# breakout.net
KiCad netlist of a schematic drawn in EAGLE
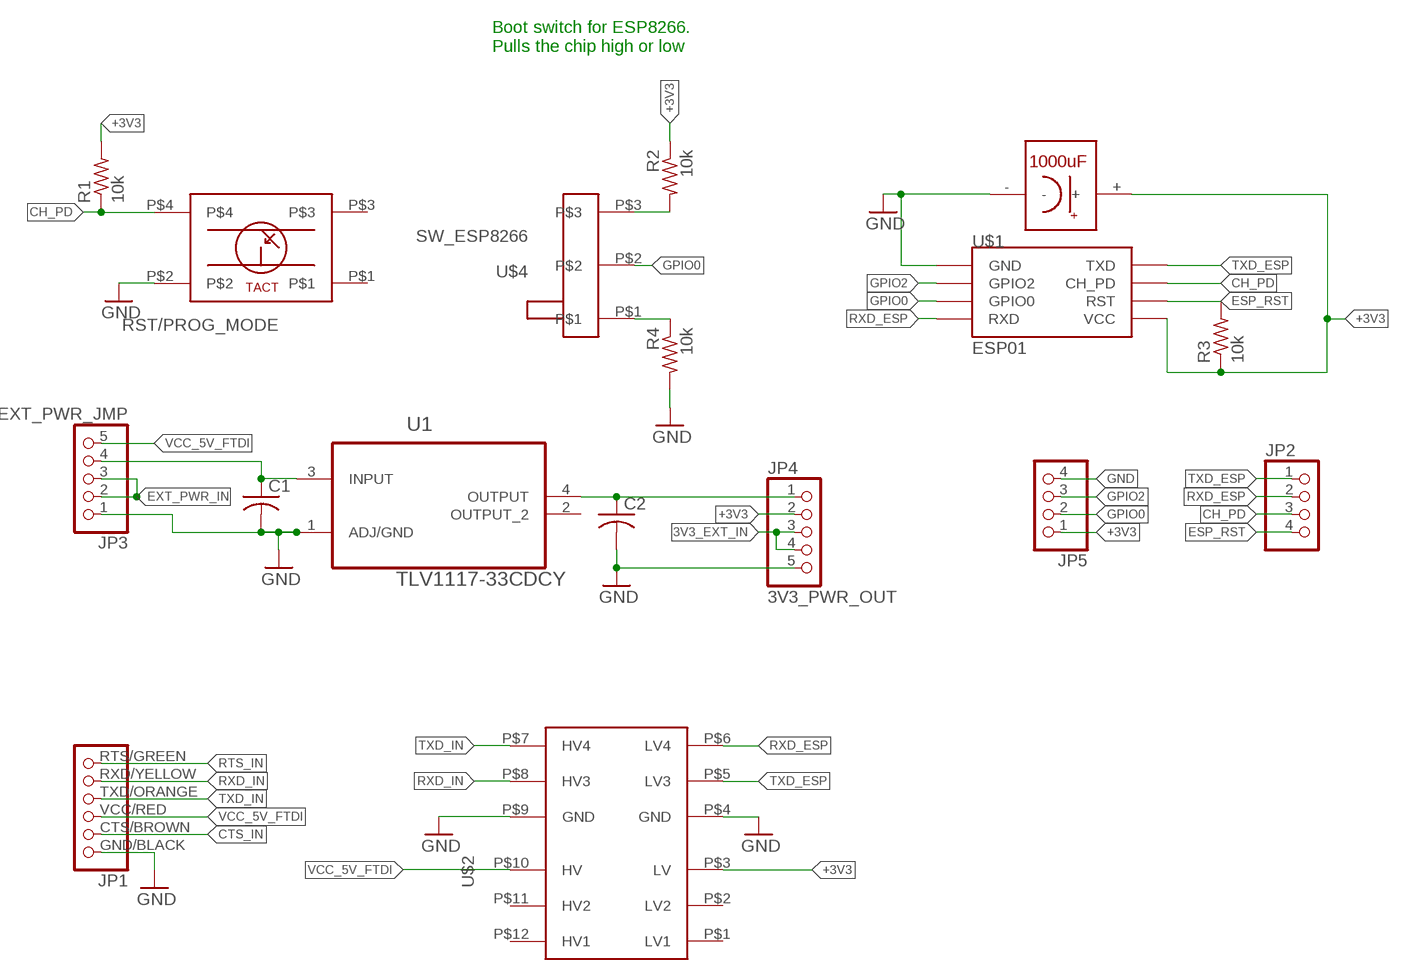
[diagram p0: schematic, sheet 1]

(export (version "E")
  (design (tool "Eeschema 10.0.6"))
  (components
    (comp (ref "C1")
      (value "C-USC0805K")
      (footprint "eagle-import:C0805K")
      (libsource (lib "eagle-import") (part "C-USC0805K"))
    )
    (comp (ref "C2")
      (value "C-USC0805K")
      (footprint "eagle-import:C0805K")
      (libsource (lib "eagle-import") (part "C-USC0805K"))
    )
    (comp (ref "JP1")
      (value "FTDI_CABLE")
      (footprint "eagle-import:FTDI_5V_SPARKFUN")
      (libsource (lib "eagle-import") (part "FTDI_CABLE"))
    )
    (comp (ref "JP2")
      (value "PINHD-1X4")
      (footprint "eagle-import:1X04")
      (libsource (lib "eagle-import") (part "PINHD-1X4"))
    )
    (comp (ref "JP3")
      (value "EXT_PWR_JMP")
      (footprint "eagle-import:1X05")
      (libsource (lib "eagle-import") (part "PINHD-1X5"))
    )
    (comp (ref "JP4")
      (value "3V3_PWR_OUT")
      (footprint "eagle-import:1X05")
      (libsource (lib "eagle-import") (part "PINHD-1X5"))
    )
    (comp (ref "JP5")
      (value "PINHD-1X4")
      (footprint "eagle-import:1X04")
      (libsource (lib "eagle-import") (part "PINHD-1X4"))
    )
    (comp (ref "R1")
      (value "10k")
      (footprint "eagle-import:R1206")
      (libsource (lib "eagle-import") (part "R-US_R1206"))
    )
    (comp (ref "R2")
      (value "10k")
      (footprint "eagle-import:R1206")
      (libsource (lib "eagle-import") (part "R-US_R1206"))
    )
    (comp (ref "R3")
      (value "10k")
      (footprint "eagle-import:R1206")
      (libsource (lib "eagle-import") (part "R-US_R1206"))
    )
    (comp (ref "R4")
      (value "10k")
      (footprint "eagle-import:R1206")
      (libsource (lib "eagle-import") (part "R-US_R1206"))
    )
    (comp (ref "RST/PROG_MODE")
      (value "TACT_SWITCH")
      (footprint "eagle-import:TACT")
      (libsource (lib "eagle-import") (part "TACT_SWITCH"))
    )
    (comp (ref "U$1")
      (value "ESP01")
      (footprint "eagle-import:ESP01")
      (libsource (lib "eagle-import") (part "ESP01"))
    )
    (comp (ref "U$2")
      (value "LVLSHIFTER")
      (footprint "eagle-import:LVLSFT_PAC")
      (libsource (lib "eagle-import") (part "LVLSHIFTER"))
    )
    (comp (ref "U$3")
      (value "TZVCAP")
      (footprint "eagle-import:TZV1000M")
      (libsource (lib "eagle-import") (part "TZVCAP"))
    )
    (comp (ref "U$4")
      (value "SW_ESP8266")
      (footprint "eagle-import:SW_PCB_ESP")
      (libsource (lib "eagle-import") (part "SW_ESP8266"))
    )
    (comp (ref "U1")
      (value "TLV1117-33CDCY")
      (footprint "eagle-import:SOT230P700X180-4N")
      (libsource (lib "eagle-import") (part "TLV1117-33CDCY"))
    )
  )
  (nets
    (net (code "1") (name "+3V3") (class "Default")
      (node (ref "JP4") (pin "2") (pinfunction "2_2") (pintype "passive"))
      (node (ref "JP5") (pin "1") (pinfunction "1_1") (pintype "passive"))
      (node (ref "R1") (pin "2") (pinfunction "2_2") (pintype "passive"))
      (node (ref "R2") (pin "1") (pinfunction "1_1") (pintype "passive"))
      (node (ref "R3") (pin "1") (pinfunction "1_1") (pintype "passive"))
      (node (ref "U$1") (pin "VCC") (pinfunction "VCC_VCC") (pintype "bidirectional"))
      (node (ref "U$2") (pin "P$3") (pinfunction "LV_P$3") (pintype "bidirectional"))
      (node (ref "U$3") (pin "+") (pinfunction "+_+") (pintype "bidirectional"))
    )
    (net (code "2") (name "3V3_EXT_IN") (class "Default")
      (node (ref "JP4") (pin "3") (pinfunction "3_3") (pintype "passive"))
      (node (ref "JP4") (pin "4") (pinfunction "4_4") (pintype "passive"))
    )
    (net (code "3") (name "CH_PD") (class "Default")
      (node (ref "JP2") (pin "3") (pinfunction "3_3") (pintype "passive"))
      (node (ref "R1") (pin "1") (pinfunction "1_1") (pintype "passive"))
      (node (ref "RST/PROG_MODE") (pin "P$4") (pinfunction "P$4_P$4") (pintype "bidirectional"))
      (node (ref "U$1") (pin "CH_PD") (pinfunction "CH_PD_CH_PD") (pintype "bidirectional"))
    )
    (net (code "4") (name "CTS_IN") (class "Default")
      (node (ref "JP1") (pin "CTS/BROWN") (pinfunction "2_CTS/BROWN") (pintype "passive"))
    )
    (net (code "5") (name "ESP_RST") (class "Default")
      (node (ref "JP2") (pin "4") (pinfunction "4_4") (pintype "passive"))
      (node (ref "R3") (pin "2") (pinfunction "2_2") (pintype "passive"))
      (node (ref "U$1") (pin "RST") (pinfunction "RST_RST") (pintype "bidirectional"))
    )
    (net (code "6") (name "EXT_PWR_IN") (class "Default")
      (node (ref "JP3") (pin "2") (pinfunction "2_2") (pintype "passive"))
      (node (ref "JP3") (pin "3") (pinfunction "3_3") (pintype "passive"))
    )
    (net (code "7") (name "GND") (class "Default")
      (node (ref "C1") (pin "2") (pinfunction "2_2") (pintype "passive"))
      (node (ref "C2") (pin "2") (pinfunction "2_2") (pintype "passive"))
      (node (ref "JP1") (pin "GND/BLACK") (pinfunction "1_GND/BLACK") (pintype "passive"))
      (node (ref "JP3") (pin "1") (pinfunction "1_1") (pintype "passive"))
      (node (ref "JP4") (pin "5") (pinfunction "5_5") (pintype "passive"))
      (node (ref "JP5") (pin "4") (pinfunction "4_4") (pintype "passive"))
      (node (ref "R4") (pin "2") (pinfunction "2_2") (pintype "passive"))
      (node (ref "RST/PROG_MODE") (pin "P$2") (pinfunction "P$2_P$2") (pintype "bidirectional"))
      (node (ref "U$1") (pin "GND") (pinfunction "GND_GND") (pintype "bidirectional"))
      (node (ref "U$2") (pin "P$4") (pinfunction "GND_P$4") (pintype "bidirectional"))
      (node (ref "U$2") (pin "P$9") (pinfunction "GND_P$9") (pintype "bidirectional"))
      (node (ref "U$3") (pin "-") (pinfunction "-_-") (pintype "bidirectional"))
      (node (ref "U1") (pin "1") (pinfunction "ADJ/GND_1") (pintype "input"))
    )
    (net (code "8") (name "GPIO0") (class "Default")
      (node (ref "JP5") (pin "2") (pinfunction "2_2") (pintype "passive"))
      (node (ref "U$1") (pin "GPIO0") (pinfunction "GPIO0_GPIO0") (pintype "bidirectional"))
      (node (ref "U$4") (pin "P$2") (pinfunction "P$2_P$2") (pintype "bidirectional"))
    )
    (net (code "9") (name "GPIO2") (class "Default")
      (node (ref "JP5") (pin "3") (pinfunction "3_3") (pintype "passive"))
      (node (ref "U$1") (pin "GPIO2") (pinfunction "GPIO2_GPIO2") (pintype "bidirectional"))
    )
    (net (code "10") (name "Net-(R2-Pad2)") (class "Default")
      (node (ref "R2") (pin "2") (pinfunction "2_2") (pintype "passive"))
      (node (ref "U$4") (pin "P$3") (pinfunction "P$3_P$3") (pintype "bidirectional"))
    )
    (net (code "11") (name "Net-(R4-Pad1)") (class "Default")
      (node (ref "R4") (pin "1") (pinfunction "1_1") (pintype "passive"))
      (node (ref "U$4") (pin "P$1") (pinfunction "P$1_P$1") (pintype "bidirectional"))
    )
    (net (code "12") (name "Net-(U1-INPUT)") (class "Default")
      (node (ref "C1") (pin "1") (pinfunction "1_1") (pintype "passive"))
      (node (ref "JP3") (pin "4") (pinfunction "4_4") (pintype "passive"))
      (node (ref "U1") (pin "3") (pinfunction "INPUT_3") (pintype "input"))
    )
    (net (code "13") (name "Net-(U1-OUTPUT)") (class "Default")
      (node (ref "C2") (pin "1") (pinfunction "1_1") (pintype "passive"))
      (node (ref "JP4") (pin "1") (pinfunction "1_1") (pintype "passive"))
      (node (ref "U1") (pin "4") (pinfunction "OUTPUT_4") (pintype "output"))
    )
    (net (code "14") (name "RTS_IN") (class "Default")
      (node (ref "JP1") (pin "RTS/GREEN") (pinfunction "6_RTS/GREEN") (pintype "passive"))
    )
    (net (code "15") (name "RXD_ESP") (class "Default")
      (node (ref "JP2") (pin "2") (pinfunction "2_2") (pintype "passive"))
      (node (ref "U$1") (pin "RX") (pinfunction "RXD_RX") (pintype "bidirectional"))
      (node (ref "U$2") (pin "P$6") (pinfunction "LV4_P$6") (pintype "bidirectional"))
    )
    (net (code "16") (name "RXD_IN") (class "Default")
      (node (ref "JP1") (pin "RXD/YELLOW") (pinfunction "5_RXD/YELLOW") (pintype "passive"))
      (node (ref "U$2") (pin "P$8") (pinfunction "HV3_P$8") (pintype "bidirectional"))
    )
    (net (code "17") (name "TXD_ESP") (class "Default")
      (node (ref "JP2") (pin "1") (pinfunction "1_1") (pintype "passive"))
      (node (ref "U$1") (pin "TX") (pinfunction "TXD_TX") (pintype "bidirectional"))
      (node (ref "U$2") (pin "P$5") (pinfunction "LV3_P$5") (pintype "bidirectional"))
    )
    (net (code "18") (name "TXD_IN") (class "Default")
      (node (ref "JP1") (pin "TXD/ORANGE") (pinfunction "4_TXD/ORANGE") (pintype "passive"))
      (node (ref "U$2") (pin "P$7") (pinfunction "HV4_P$7") (pintype "bidirectional"))
    )
    (net (code "19") (name "VCC_5V_FTDI") (class "Default")
      (node (ref "JP1") (pin "VCC/RED") (pinfunction "3_VCC/RED") (pintype "passive"))
      (node (ref "JP3") (pin "5") (pinfunction "5_5") (pintype "passive"))
      (node (ref "U$2") (pin "P$10") (pinfunction "HV_P$10") (pintype "bidirectional"))
    )
    (net (code "20") (name "unconnected-(RST/PROG_MODE-PadP$1)") (class "Default")
      (node (ref "RST/PROG_MODE") (pin "P$1") (pinfunction "P$1_P$1") (pintype "bidirectional"))
    )
    (net (code "21") (name "unconnected-(RST/PROG_MODE-PadP$3)") (class "Default")
      (node (ref "RST/PROG_MODE") (pin "P$3") (pinfunction "P$3_P$3") (pintype "bidirectional"))
    )
    (net (code "22") (name "unconnected-(U$2-HV1-PadP$12)") (class "Default")
      (node (ref "U$2") (pin "P$12") (pinfunction "HV1_P$12") (pintype "bidirectional"))
    )
    (net (code "23") (name "unconnected-(U$2-HV2-PadP$11)") (class "Default")
      (node (ref "U$2") (pin "P$11") (pinfunction "HV2_P$11") (pintype "bidirectional"))
    )
    (net (code "24") (name "unconnected-(U$2-LV1-PadP$1)") (class "Default")
      (node (ref "U$2") (pin "P$1") (pinfunction "LV1_P$1") (pintype "bidirectional"))
    )
    (net (code "25") (name "unconnected-(U$2-LV2-PadP$2)") (class "Default")
      (node (ref "U$2") (pin "P$2") (pinfunction "LV2_P$2") (pintype "bidirectional"))
    )
    (net (code "26") (name "unconnected-(U1-OUTPUT_2-Pad2)") (class "Default")
      (node (ref "U1") (pin "2") (pinfunction "OUTPUT_2_2") (pintype "output"))
    )
  )
)
